# Ffrydiau_core.net
KiCad netlist of a schematic drawn in EAGLE
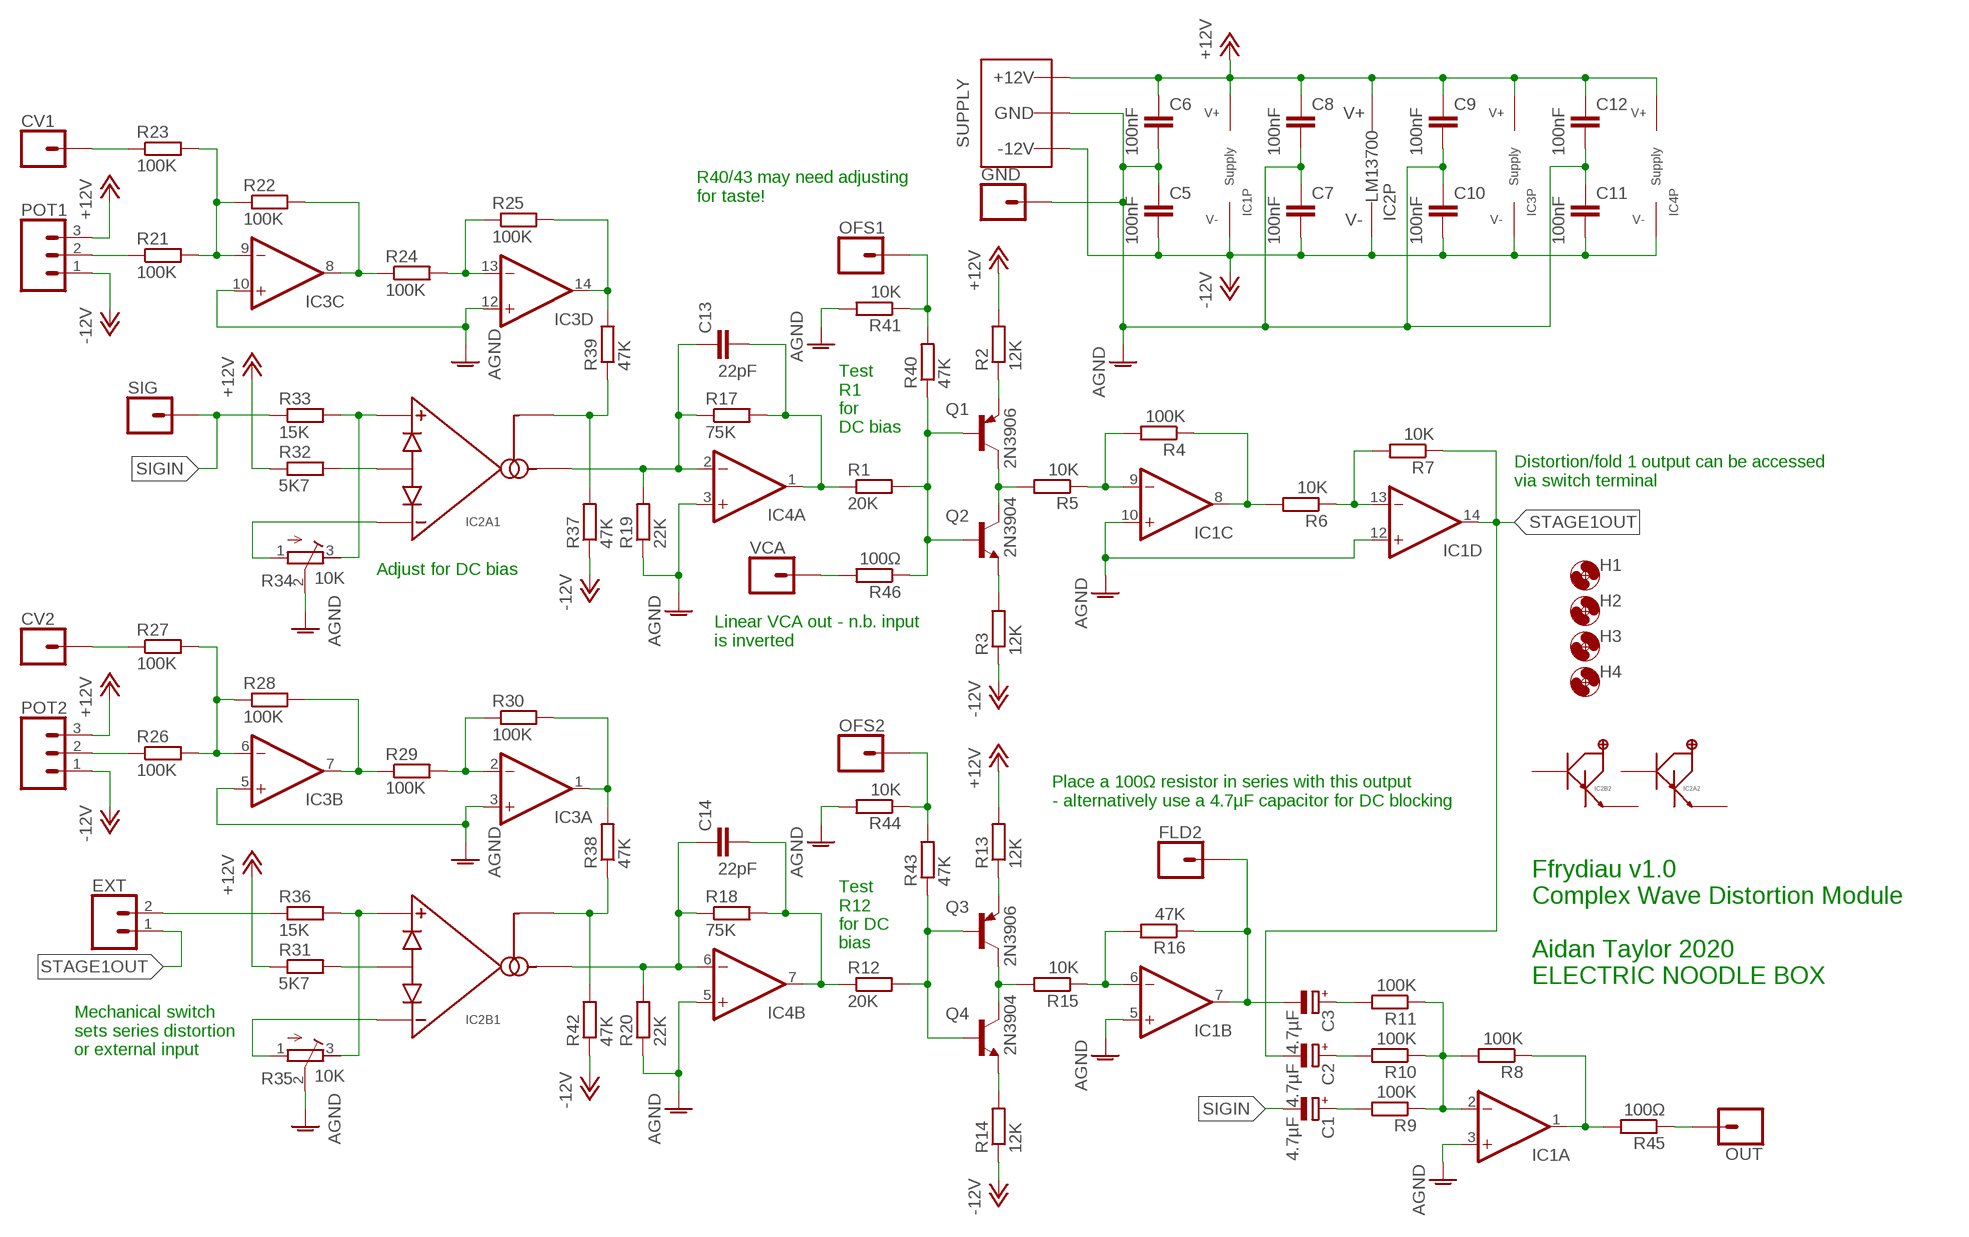
[diagram p0: schematic, sheet 1]

(export (version "E")
  (design (tool "Eeschema 10.0.6"))
  (components
    (comp (ref "C1")
      (value "4.7µF")
      (footprint "eagle-import:E2,5-6E")
      (libsource (lib "eagle-import") (part "CPOL-EUE2,5-6E"))
    )
    (comp (ref "C2")
      (value "4.7µF")
      (footprint "eagle-import:E2,5-6E")
      (libsource (lib "eagle-import") (part "CPOL-EUE2,5-6E"))
    )
    (comp (ref "C3")
      (value "4.7µF")
      (footprint "eagle-import:E2,5-6E")
      (libsource (lib "eagle-import") (part "CPOL-EUE2,5-6E"))
    )
    (comp (ref "C5")
      (value "100nF")
      (footprint "eagle-import:C050-025X075")
      (libsource (lib "eagle-import") (part "C-EU050-025X075"))
    )
    (comp (ref "C6")
      (value "100nF")
      (footprint "eagle-import:C050-025X075")
      (libsource (lib "eagle-import") (part "C-EU050-025X075"))
    )
    (comp (ref "C7")
      (value "100nF")
      (footprint "eagle-import:C050-025X075")
      (libsource (lib "eagle-import") (part "C-EU050-025X075"))
    )
    (comp (ref "C8")
      (value "100nF")
      (footprint "eagle-import:C050-025X075")
      (libsource (lib "eagle-import") (part "C-EU050-025X075"))
    )
    (comp (ref "C9")
      (value "100nF")
      (footprint "eagle-import:C050-025X075")
      (libsource (lib "eagle-import") (part "C-EU050-025X075"))
    )
    (comp (ref "C10")
      (value "100nF")
      (footprint "eagle-import:C050-025X075")
      (libsource (lib "eagle-import") (part "C-EU050-025X075"))
    )
    (comp (ref "C11")
      (value "100nF")
      (footprint "eagle-import:C050-025X075")
      (libsource (lib "eagle-import") (part "C-EU050-025X075"))
    )
    (comp (ref "C12")
      (value "100nF")
      (footprint "eagle-import:C050-025X075")
      (libsource (lib "eagle-import") (part "C-EU050-025X075"))
    )
    (comp (ref "C13")
      (value "22pF")
      (footprint "eagle-import:C050-025X075")
      (libsource (lib "eagle-import") (part "C-EU050-025X075"))
    )
    (comp (ref "C14")
      (value "22pF")
      (footprint "eagle-import:C050-025X075")
      (libsource (lib "eagle-import") (part "C-EU050-025X075"))
    )
    (comp (ref "CV1")
      (value "1XWIREPAD")
      (footprint "eagle-import:1X01")
      (libsource (lib "eagle-import") (part "1XWIREPAD"))
    )
    (comp (ref "CV2")
      (value "1XWIREPAD")
      (footprint "eagle-import:1X01")
      (libsource (lib "eagle-import") (part "1XWIREPAD"))
    )
    (comp (ref "EXT")
      (value "2XWIREPAD")
      (footprint "eagle-import:1X02")
      (libsource (lib "eagle-import") (part "2XWIREPAD"))
    )
    (comp (ref "FLD2")
      (value "1XWIREPAD")
      (footprint "eagle-import:1X01")
      (libsource (lib "eagle-import") (part "1XWIREPAD"))
    )
    (comp (ref "GND")
      (value "1XWIREPAD")
      (footprint "eagle-import:1X01")
      (libsource (lib "eagle-import") (part "1XWIREPAD"))
    )
    (comp (ref "H1")
      (value "MOUNT-HOLE3.2")
      (footprint "eagle-import:3,2")
      (libsource (lib "eagle-import") (part "MOUNT-HOLE3.2"))
    )
    (comp (ref "H2")
      (value "MOUNT-HOLE3.2")
      (footprint "eagle-import:3,2")
      (libsource (lib "eagle-import") (part "MOUNT-HOLE3.2"))
    )
    (comp (ref "H3")
      (value "MOUNT-HOLE3.2")
      (footprint "eagle-import:3,2")
      (libsource (lib "eagle-import") (part "MOUNT-HOLE3.2"))
    )
    (comp (ref "H4")
      (value "MOUNT-HOLE3.2")
      (footprint "eagle-import:3,2")
      (libsource (lib "eagle-import") (part "MOUNT-HOLE3.2"))
    )
    (comp (ref "IC1")
      (value "TL0X4DIL")
      (footprint "eagle-import:DIL14")
      (libsource (lib "eagle-import") (part "TL0X4DIL"))
    )
    (comp (ref "IC2")
      (value "LM13700DIL")
      (footprint "eagle-import:DIL16")
      (libsource (lib "eagle-import") (part "LM13700DIL"))
    )
    (comp (ref "IC3")
      (value "TL0X4DIL")
      (footprint "eagle-import:DIL14")
      (libsource (lib "eagle-import") (part "TL0X4DIL"))
    )
    (comp (ref "IC4")
      (value "TL0X2DIL")
      (footprint "eagle-import:DIL08")
      (libsource (lib "eagle-import") (part "TL0X2DIL"))
    )
    (comp (ref "OFS1")
      (value "1XWIREPAD")
      (footprint "eagle-import:1X01")
      (libsource (lib "eagle-import") (part "1XWIREPAD"))
    )
    (comp (ref "OFS2")
      (value "1XWIREPAD")
      (footprint "eagle-import:1X01")
      (libsource (lib "eagle-import") (part "1XWIREPAD"))
    )
    (comp (ref "OUT")
      (value "1XWIREPAD")
      (footprint "eagle-import:1X01")
      (libsource (lib "eagle-import") (part "1XWIREPAD"))
    )
    (comp (ref "POT1")
      (value "3XWIREPAD")
      (footprint "eagle-import:1X03")
      (libsource (lib "eagle-import") (part "3XWIREPAD"))
    )
    (comp (ref "POT2")
      (value "3XWIREPAD")
      (footprint "eagle-import:1X03")
      (libsource (lib "eagle-import") (part "3XWIREPAD"))
    )
    (comp (ref "Q1")
      (value "2N3906")
      (footprint "eagle-import:TO92")
      (libsource (lib "eagle-import") (part "2N3906"))
    )
    (comp (ref "Q2")
      (value "2N3904")
      (footprint "eagle-import:TO92")
      (libsource (lib "eagle-import") (part "2N3904"))
    )
    (comp (ref "Q3")
      (value "2N3906")
      (footprint "eagle-import:TO92")
      (libsource (lib "eagle-import") (part "2N3906"))
    )
    (comp (ref "Q4")
      (value "2N3904")
      (footprint "eagle-import:TO92")
      (libsource (lib "eagle-import") (part "2N3904"))
    )
    (comp (ref "R1")
      (value "20K")
      (footprint "eagle-import:0207_10")
      (libsource (lib "eagle-import") (part "R-EU_0207/10"))
    )
    (comp (ref "R2")
      (value "12K")
      (footprint "eagle-import:0207_10")
      (libsource (lib "eagle-import") (part "R-EU_0207/10"))
    )
    (comp (ref "R3")
      (value "12K")
      (footprint "eagle-import:0207_10")
      (libsource (lib "eagle-import") (part "R-EU_0207/10"))
    )
    (comp (ref "R4")
      (value "100K")
      (footprint "eagle-import:0207_10")
      (libsource (lib "eagle-import") (part "R-EU_0207/10"))
    )
    (comp (ref "R5")
      (value "10K")
      (footprint "eagle-import:0207_10")
      (libsource (lib "eagle-import") (part "R-EU_0207/10"))
    )
    (comp (ref "R6")
      (value "10K")
      (footprint "eagle-import:0207_10")
      (libsource (lib "eagle-import") (part "R-EU_0207/10"))
    )
    (comp (ref "R7")
      (value "10K")
      (footprint "eagle-import:0207_10")
      (libsource (lib "eagle-import") (part "R-EU_0207/10"))
    )
    (comp (ref "R8")
      (value "100K")
      (footprint "eagle-import:0207_10")
      (libsource (lib "eagle-import") (part "R-EU_0207/10"))
    )
    (comp (ref "R9")
      (value "100K")
      (footprint "eagle-import:0207_10")
      (libsource (lib "eagle-import") (part "R-EU_0207/10"))
    )
    (comp (ref "R10")
      (value "100K")
      (footprint "eagle-import:0207_10")
      (libsource (lib "eagle-import") (part "R-EU_0207/10"))
    )
    (comp (ref "R11")
      (value "100K")
      (footprint "eagle-import:0207_10")
      (libsource (lib "eagle-import") (part "R-EU_0207/10"))
    )
    (comp (ref "R12")
      (value "20K")
      (footprint "eagle-import:0207_10")
      (libsource (lib "eagle-import") (part "R-EU_0207/10"))
    )
    (comp (ref "R13")
      (value "12K")
      (footprint "eagle-import:0207_10")
      (libsource (lib "eagle-import") (part "R-EU_0207/10"))
    )
    (comp (ref "R14")
      (value "12K")
      (footprint "eagle-import:0207_10")
      (libsource (lib "eagle-import") (part "R-EU_0207/10"))
    )
    (comp (ref "R15")
      (value "10K")
      (footprint "eagle-import:0207_10")
      (libsource (lib "eagle-import") (part "R-EU_0207/10"))
    )
    (comp (ref "R16")
      (value "47K")
      (footprint "eagle-import:0207_10")
      (libsource (lib "eagle-import") (part "R-EU_0207/10"))
    )
    (comp (ref "R17")
      (value "75K")
      (footprint "eagle-import:0207_10")
      (libsource (lib "eagle-import") (part "R-EU_0207/10"))
    )
    (comp (ref "R18")
      (value "75K")
      (footprint "eagle-import:0207_10")
      (libsource (lib "eagle-import") (part "R-EU_0207/10"))
    )
    (comp (ref "R19")
      (value "22K")
      (footprint "eagle-import:0207_10")
      (libsource (lib "eagle-import") (part "R-EU_0207/10"))
    )
    (comp (ref "R20")
      (value "22K")
      (footprint "eagle-import:0207_10")
      (libsource (lib "eagle-import") (part "R-EU_0207/10"))
    )
    (comp (ref "R21")
      (value "100K")
      (footprint "eagle-import:0207_10")
      (libsource (lib "eagle-import") (part "R-EU_0207/10"))
    )
    (comp (ref "R22")
      (value "100K")
      (footprint "eagle-import:0207_10")
      (libsource (lib "eagle-import") (part "R-EU_0207/10"))
    )
    (comp (ref "R23")
      (value "100K")
      (footprint "eagle-import:0207_10")
      (libsource (lib "eagle-import") (part "R-EU_0207/10"))
    )
    (comp (ref "R24")
      (value "100K")
      (footprint "eagle-import:0207_10")
      (libsource (lib "eagle-import") (part "R-EU_0207/10"))
    )
    (comp (ref "R25")
      (value "100K")
      (footprint "eagle-import:0207_10")
      (libsource (lib "eagle-import") (part "R-EU_0207/10"))
    )
    (comp (ref "R26")
      (value "100K")
      (footprint "eagle-import:0207_10")
      (libsource (lib "eagle-import") (part "R-EU_0207/10"))
    )
    (comp (ref "R27")
      (value "100K")
      (footprint "eagle-import:0207_10")
      (libsource (lib "eagle-import") (part "R-EU_0207/10"))
    )
    (comp (ref "R28")
      (value "100K")
      (footprint "eagle-import:0207_10")
      (libsource (lib "eagle-import") (part "R-EU_0207/10"))
    )
    (comp (ref "R29")
      (value "100K")
      (footprint "eagle-import:0207_10")
      (libsource (lib "eagle-import") (part "R-EU_0207/10"))
    )
    (comp (ref "R30")
      (value "100K")
      (footprint "eagle-import:0207_10")
      (libsource (lib "eagle-import") (part "R-EU_0207/10"))
    )
    (comp (ref "R31")
      (value "5K7")
      (footprint "eagle-import:0207_10")
      (libsource (lib "eagle-import") (part "R-EU_0207/10"))
    )
    (comp (ref "R32")
      (value "5K7")
      (footprint "eagle-import:0207_10")
      (libsource (lib "eagle-import") (part "R-EU_0207/10"))
    )
    (comp (ref "R33")
      (value "15K")
      (footprint "eagle-import:0207_10")
      (libsource (lib "eagle-import") (part "R-EU_0207/10"))
    )
    (comp (ref "R34")
      (value "10K")
      (footprint "eagle-import:RTRIM3296W")
      (libsource (lib "eagle-import") (part "R-TRIMM3296W"))
    )
    (comp (ref "R35")
      (value "10K")
      (footprint "eagle-import:RTRIM3296W")
      (libsource (lib "eagle-import") (part "R-TRIMM3296W"))
    )
    (comp (ref "R36")
      (value "15K")
      (footprint "eagle-import:0207_10")
      (libsource (lib "eagle-import") (part "R-EU_0207/10"))
    )
    (comp (ref "R37")
      (value "47K")
      (footprint "eagle-import:0207_10")
      (libsource (lib "eagle-import") (part "R-EU_0207/10"))
    )
    (comp (ref "R38")
      (value "47K")
      (footprint "eagle-import:0207_10")
      (libsource (lib "eagle-import") (part "R-EU_0207/10"))
    )
    (comp (ref "R39")
      (value "47K")
      (footprint "eagle-import:0207_10")
      (libsource (lib "eagle-import") (part "R-EU_0207/10"))
    )
    (comp (ref "R40")
      (value "47K")
      (footprint "eagle-import:0207_10")
      (libsource (lib "eagle-import") (part "R-EU_0207/10"))
    )
    (comp (ref "R41")
      (value "10K")
      (footprint "eagle-import:0207_10")
      (libsource (lib "eagle-import") (part "R-EU_0207/10"))
    )
    (comp (ref "R42")
      (value "47K")
      (footprint "eagle-import:0207_10")
      (libsource (lib "eagle-import") (part "R-EU_0207/10"))
    )
    (comp (ref "R43")
      (value "47K")
      (footprint "eagle-import:0207_10")
      (libsource (lib "eagle-import") (part "R-EU_0207/10"))
    )
    (comp (ref "R44")
      (value "10K")
      (footprint "eagle-import:0207_10")
      (libsource (lib "eagle-import") (part "R-EU_0207/10"))
    )
    (comp (ref "R45")
      (value "100Ω")
      (footprint "eagle-import:0207_10")
      (libsource (lib "eagle-import") (part "R-EU_0207/10"))
    )
    (comp (ref "R46")
      (value "100Ω")
      (footprint "eagle-import:0207_10")
      (libsource (lib "eagle-import") (part "R-EU_0207/10"))
    )
    (comp (ref "SIG")
      (value "1XWIREPAD")
      (footprint "eagle-import:1X01")
      (libsource (lib "eagle-import") (part "1XWIREPAD"))
    )
    (comp (ref "VCA")
      (value "1XWIREPAD")
      (footprint "eagle-import:1X01")
      (libsource (lib "eagle-import") (part "1XWIREPAD"))
    )
    (comp (ref "WP1")
      (value "COMBO_SUPPLY_HEADER")
      (footprint "eagle-import:COMBINED_POWER")
      (libsource (lib "eagle-import") (part "COMBO_SUPPLY_HEADER"))
    )
  )
  (nets
    (net (code "1") (name "+12V") (class "Default")
      (node (ref "C12") (pin "1") (pinfunction "1_1") (pintype "passive"))
      (node (ref "C6") (pin "1") (pinfunction "1_1") (pintype "passive"))
      (node (ref "C8") (pin "1") (pinfunction "1_1") (pintype "passive"))
      (node (ref "C9") (pin "1") (pinfunction "1_1") (pintype "passive"))
      (node (ref "IC1") (pin "4") (pinfunction "V+_4") (pintype "bidirectional"))
      (node (ref "IC2") (pin "11") (pinfunction "V+_11") (pintype "power_in"))
      (node (ref "IC3") (pin "4") (pinfunction "V+_4") (pintype "bidirectional"))
      (node (ref "IC4") (pin "8") (pinfunction "V+_8") (pintype "bidirectional"))
      (node (ref "POT1") (pin "3") (pinfunction "3_3") (pintype "passive"))
      (node (ref "POT2") (pin "3") (pinfunction "3_3") (pintype "passive"))
      (node (ref "R13") (pin "2") (pinfunction "2_2") (pintype "passive"))
      (node (ref "R2") (pin "2") (pinfunction "2_2") (pintype "passive"))
      (node (ref "R31") (pin "1") (pinfunction "1_1") (pintype "passive"))
      (node (ref "R32") (pin "1") (pinfunction "1_1") (pintype "passive"))
      (node (ref "WP1") (pin "V+1") (pinfunction "V++_V+1") (pintype "power_in"))
      (node (ref "WP1") (pin "V+2") (pinfunction "V++_V+2") (pintype "power_in"))
      (node (ref "WP1") (pin "V+3") (pinfunction "V++_V+3") (pintype "power_in"))
    )
    (net (code "2") (name "-12V") (class "Default")
      (node (ref "C10") (pin "2") (pinfunction "2_2") (pintype "passive"))
      (node (ref "C11") (pin "2") (pinfunction "2_2") (pintype "passive"))
      (node (ref "C5") (pin "2") (pinfunction "2_2") (pintype "passive"))
      (node (ref "C7") (pin "2") (pinfunction "2_2") (pintype "passive"))
      (node (ref "IC1") (pin "11") (pinfunction "V-_11") (pintype "bidirectional"))
      (node (ref "IC2") (pin "6") (pinfunction "V-_6") (pintype "power_in"))
      (node (ref "IC3") (pin "11") (pinfunction "V-_11") (pintype "bidirectional"))
      (node (ref "IC4") (pin "4") (pinfunction "V-_4") (pintype "bidirectional"))
      (node (ref "POT1") (pin "1") (pinfunction "1_1") (pintype "passive"))
      (node (ref "POT2") (pin "1") (pinfunction "1_1") (pintype "passive"))
      (node (ref "R14") (pin "1") (pinfunction "1_1") (pintype "passive"))
      (node (ref "R3") (pin "1") (pinfunction "1_1") (pintype "passive"))
      (node (ref "R37") (pin "1") (pinfunction "1_1") (pintype "passive"))
      (node (ref "R42") (pin "1") (pinfunction "1_1") (pintype "passive"))
      (node (ref "WP1") (pin "V-1") (pinfunction "V--_V-1") (pintype "power_in"))
      (node (ref "WP1") (pin "V-2") (pinfunction "V--_V-2") (pintype "power_in"))
      (node (ref "WP1") (pin "V-3") (pinfunction "V--_V-3") (pintype "power_in"))
    )
    (net (code "3") (name "AGND") (class "Default")
      (node (ref "C10") (pin "1") (pinfunction "1_1") (pintype "passive"))
      (node (ref "C11") (pin "1") (pinfunction "1_1") (pintype "passive"))
      (node (ref "C12") (pin "2") (pinfunction "2_2") (pintype "passive"))
      (node (ref "C5") (pin "1") (pinfunction "1_1") (pintype "passive"))
      (node (ref "C6") (pin "2") (pinfunction "2_2") (pintype "passive"))
      (node (ref "C7") (pin "1") (pinfunction "1_1") (pintype "passive"))
      (node (ref "C8") (pin "2") (pinfunction "2_2") (pintype "passive"))
      (node (ref "C9") (pin "2") (pinfunction "2_2") (pintype "passive"))
      (node (ref "GND") (pin "1") (pinfunction "1_1") (pintype "passive"))
      (node (ref "IC1") (pin "10") (pinfunction "+IN_10") (pintype "input"))
      (node (ref "IC1") (pin "12") (pinfunction "+IN_12") (pintype "input"))
      (node (ref "IC1") (pin "3") (pinfunction "+IN_3") (pintype "input"))
      (node (ref "IC1") (pin "5") (pinfunction "+IN_5") (pintype "input"))
      (node (ref "IC3") (pin "10") (pinfunction "+IN_10") (pintype "input"))
      (node (ref "IC3") (pin "12") (pinfunction "+IN_12") (pintype "input"))
      (node (ref "IC3") (pin "3") (pinfunction "+IN_3") (pintype "input"))
      (node (ref "IC3") (pin "5") (pinfunction "+IN_5") (pintype "input"))
      (node (ref "IC4") (pin "3") (pinfunction "+IN_3") (pintype "input"))
      (node (ref "IC4") (pin "5") (pinfunction "+IN_5") (pintype "input"))
      (node (ref "R19") (pin "1") (pinfunction "1_1") (pintype "passive"))
      (node (ref "R20") (pin "1") (pinfunction "1_1") (pintype "passive"))
      (node (ref "R34") (pin "2") (pinfunction "S_2") (pintype "passive"))
      (node (ref "R35") (pin "2") (pinfunction "S_2") (pintype "passive"))
      (node (ref "R41") (pin "2") (pinfunction "2_2") (pintype "passive"))
      (node (ref "R44") (pin "2") (pinfunction "2_2") (pintype "passive"))
      (node (ref "WP1") (pin "GND1") (pinfunction "AGND_GND1") (pintype "power_in"))
      (node (ref "WP1") (pin "GND2") (pinfunction "AGND_GND2") (pintype "power_in"))
      (node (ref "WP1") (pin "GND3") (pinfunction "AGND_GND3") (pintype "power_in"))
      (node (ref "WP1") (pin "GND4") (pinfunction "AGND_GND4") (pintype "power_in"))
      (node (ref "WP1") (pin "GND5") (pinfunction "AGND_GND5") (pintype "power_in"))
      (node (ref "WP1") (pin "GND6") (pinfunction "AGND_GND6") (pintype "power_in"))
      (node (ref "WP1") (pin "GND7") (pinfunction "AGND_GND7") (pintype "power_in"))
      (node (ref "WP1") (pin "GND8") (pinfunction "AGND_GND8") (pintype "power_in"))
    )
    (net (code "4") (name "Net-(C1-Pad+)") (class "Default")
      (node (ref "C1") (pin "+") (pinfunction "+_+") (pintype "passive"))
      (node (ref "R9") (pin "2") (pinfunction "2_2") (pintype "passive"))
    )
    (net (code "5") (name "Net-(C2-Pad+)") (class "Default")
      (node (ref "C2") (pin "+") (pinfunction "+_+") (pintype "passive"))
      (node (ref "R10") (pin "2") (pinfunction "2_2") (pintype "passive"))
    )
    (net (code "6") (name "Net-(C3-Pad+)") (class "Default")
      (node (ref "C3") (pin "+") (pinfunction "+_+") (pintype "passive"))
      (node (ref "R11") (pin "2") (pinfunction "2_2") (pintype "passive"))
    )
    (net (code "7") (name "Net-(CV1-Pad1)") (class "Default")
      (node (ref "CV1") (pin "1") (pinfunction "1_1") (pintype "passive"))
      (node (ref "R23") (pin "1") (pinfunction "1_1") (pintype "passive"))
    )
    (net (code "8") (name "Net-(CV2-Pad1)") (class "Default")
      (node (ref "CV2") (pin "1") (pinfunction "1_1") (pintype "passive"))
      (node (ref "R27") (pin "1") (pinfunction "1_1") (pintype "passive"))
    )
    (net (code "9") (name "Net-(EXT-Pad2)") (class "Default")
      (node (ref "EXT") (pin "2") (pinfunction "2_2") (pintype "passive"))
      (node (ref "R36") (pin "1") (pinfunction "1_1") (pintype "passive"))
    )
    (net (code "10") (name "Net-(IC1A--IN)") (class "Default")
      (node (ref "IC1") (pin "2") (pinfunction "-IN_2") (pintype "input"))
      (node (ref "R10") (pin "1") (pinfunction "1_1") (pintype "passive"))
      (node (ref "R11") (pin "1") (pinfunction "1_1") (pintype "passive"))
      (node (ref "R8") (pin "2") (pinfunction "2_2") (pintype "passive"))
      (node (ref "R9") (pin "1") (pinfunction "1_1") (pintype "passive"))
    )
    (net (code "11") (name "Net-(IC1A-OUT)") (class "Default")
      (node (ref "IC1") (pin "1") (pinfunction "OUT_1") (pintype "output"))
      (node (ref "R45") (pin "2") (pinfunction "2_2") (pintype "passive"))
      (node (ref "R8") (pin "1") (pinfunction "1_1") (pintype "passive"))
    )
    (net (code "12") (name "Net-(IC1B--IN)") (class "Default")
      (node (ref "IC1") (pin "6") (pinfunction "-IN_6") (pintype "input"))
      (node (ref "R15") (pin "1") (pinfunction "1_1") (pintype "passive"))
      (node (ref "R16") (pin "2") (pinfunction "2_2") (pintype "passive"))
    )
    (net (code "13") (name "Net-(IC1B-OUT)") (class "Default")
      (node (ref "C3") (pin "-") (pinfunction "-_-") (pintype "passive"))
      (node (ref "FLD2") (pin "1") (pinfunction "1_1") (pintype "passive"))
      (node (ref "IC1") (pin "7") (pinfunction "OUT_7") (pintype "output"))
      (node (ref "R16") (pin "1") (pinfunction "1_1") (pintype "passive"))
    )
    (net (code "14") (name "Net-(IC1C--IN)") (class "Default")
      (node (ref "IC1") (pin "9") (pinfunction "-IN_9") (pintype "input"))
      (node (ref "R4") (pin "2") (pinfunction "2_2") (pintype "passive"))
      (node (ref "R5") (pin "1") (pinfunction "1_1") (pintype "passive"))
    )
    (net (code "15") (name "Net-(IC1C-OUT)") (class "Default")
      (node (ref "IC1") (pin "8") (pinfunction "OUT_8") (pintype "output"))
      (node (ref "R4") (pin "1") (pinfunction "1_1") (pintype "passive"))
      (node (ref "R6") (pin "2") (pinfunction "2_2") (pintype "passive"))
    )
    (net (code "16") (name "Net-(IC1D--IN)") (class "Default")
      (node (ref "IC1") (pin "13") (pinfunction "-IN_13") (pintype "input"))
      (node (ref "R6") (pin "1") (pinfunction "1_1") (pintype "passive"))
      (node (ref "R7") (pin "2") (pinfunction "2_2") (pintype "passive"))
    )
    (net (code "17") (name "Net-(IC2A-AMP+)") (class "Default")
      (node (ref "IC2") (pin "3") (pinfunction "AMP+_3") (pintype "input"))
      (node (ref "R33") (pin "2") (pinfunction "2_2") (pintype "passive"))
      (node (ref "R34") (pin "3") (pinfunction "E_3") (pintype "passive"))
    )
    (net (code "18") (name "Net-(IC2A-AMP-)") (class "Default")
      (node (ref "IC2") (pin "4") (pinfunction "AMP-_4") (pintype "input"))
      (node (ref "R34") (pin "1") (pinfunction "A_1") (pintype "passive"))
    )
    (net (code "19") (name "Net-(IC2A-AMPBIAS)") (class "Default")
      (node (ref "IC2") (pin "1") (pinfunction "AMPBIAS_1") (pintype "input"))
      (node (ref "R37") (pin "2") (pinfunction "2_2") (pintype "passive"))
      (node (ref "R39") (pin "1") (pinfunction "1_1") (pintype "passive"))
    )
    (net (code "20") (name "Net-(IC2A-AMPOUT)") (class "Default")
      (node (ref "C13") (pin "1") (pinfunction "1_1") (pintype "passive"))
      (node (ref "IC2") (pin "5") (pinfunction "AMPOUT_5") (pintype "output"))
      (node (ref "IC4") (pin "2") (pinfunction "-IN_2") (pintype "input"))
      (node (ref "R17") (pin "1") (pinfunction "1_1") (pintype "passive"))
      (node (ref "R19") (pin "2") (pinfunction "2_2") (pintype "passive"))
    )
    (net (code "21") (name "Net-(IC2A-DIODES)") (class "Default")
      (node (ref "IC2") (pin "2") (pinfunction "DIODES_2") (pintype "input"))
      (node (ref "R32") (pin "2") (pinfunction "2_2") (pintype "passive"))
    )
    (net (code "22") (name "Net-(IC2C-AMP+)") (class "Default")
      (node (ref "IC2") (pin "14") (pinfunction "AMP+_14") (pintype "input"))
      (node (ref "R35") (pin "3") (pinfunction "E_3") (pintype "passive"))
      (node (ref "R36") (pin "2") (pinfunction "2_2") (pintype "passive"))
    )
    (net (code "23") (name "Net-(IC2C-AMP-)") (class "Default")
      (node (ref "IC2") (pin "13") (pinfunction "AMP-_13") (pintype "input"))
      (node (ref "R35") (pin "1") (pinfunction "A_1") (pintype "passive"))
    )
    (net (code "24") (name "Net-(IC2C-AMPBIAS)") (class "Default")
      (node (ref "IC2") (pin "16") (pinfunction "AMPBIAS_16") (pintype "input"))
      (node (ref "R38") (pin "1") (pinfunction "1_1") (pintype "passive"))
      (node (ref "R42") (pin "2") (pinfunction "2_2") (pintype "passive"))
    )
    (net (code "25") (name "Net-(IC2C-AMPOUT)") (class "Default")
      (node (ref "C14") (pin "1") (pinfunction "1_1") (pintype "passive"))
      (node (ref "IC2") (pin "12") (pinfunction "AMPOUT_12") (pintype "output"))
      (node (ref "IC4") (pin "6") (pinfunction "-IN_6") (pintype "input"))
      (node (ref "R18") (pin "1") (pinfunction "1_1") (pintype "passive"))
      (node (ref "R20") (pin "2") (pinfunction "2_2") (pintype "passive"))
    )
    (net (code "26") (name "Net-(IC2C-DIODES)") (class "Default")
      (node (ref "IC2") (pin "15") (pinfunction "DIODES_15") (pintype "input"))
      (node (ref "R31") (pin "2") (pinfunction "2_2") (pintype "passive"))
    )
    (net (code "27") (name "Net-(IC3A--IN)") (class "Default")
      (node (ref "IC3") (pin "2") (pinfunction "-IN_2") (pintype "input"))
      (node (ref "R29") (pin "2") (pinfunction "2_2") (pintype "passive"))
      (node (ref "R30") (pin "1") (pinfunction "1_1") (pintype "passive"))
    )
    (net (code "28") (name "Net-(IC3A-OUT)") (class "Default")
      (node (ref "IC3") (pin "1") (pinfunction "OUT_1") (pintype "output"))
      (node (ref "R30") (pin "2") (pinfunction "2_2") (pintype "passive"))
      (node (ref "R38") (pin "2") (pinfunction "2_2") (pintype "passive"))
    )
    (net (code "29") (name "Net-(IC3B--IN)") (class "Default")
      (node (ref "IC3") (pin "6") (pinfunction "-IN_6") (pintype "input"))
      (node (ref "R26") (pin "2") (pinfunction "2_2") (pintype "passive"))
      (node (ref "R27") (pin "2") (pinfunction "2_2") (pintype "passive"))
      (node (ref "R28") (pin "1") (pinfunction "1_1") (pintype "passive"))
    )
    (net (code "30") (name "Net-(IC3B-OUT)") (class "Default")
      (node (ref "IC3") (pin "7") (pinfunction "OUT_7") (pintype "output"))
      (node (ref "R28") (pin "2") (pinfunction "2_2") (pintype "passive"))
      (node (ref "R29") (pin "1") (pinfunction "1_1") (pintype "passive"))
    )
    (net (code "31") (name "Net-(IC3C--IN)") (class "Default")
      (node (ref "IC3") (pin "9") (pinfunction "-IN_9") (pintype "input"))
      (node (ref "R21") (pin "2") (pinfunction "2_2") (pintype "passive"))
      (node (ref "R22") (pin "1") (pinfunction "1_1") (pintype "passive"))
      (node (ref "R23") (pin "2") (pinfunction "2_2") (pintype "passive"))
    )
    (net (code "32") (name "Net-(IC3C-OUT)") (class "Default")
      (node (ref "IC3") (pin "8") (pinfunction "OUT_8") (pintype "output"))
      (node (ref "R22") (pin "2") (pinfunction "2_2") (pintype "passive"))
      (node (ref "R24") (pin "1") (pinfunction "1_1") (pintype "passive"))
    )
    (net (code "33") (name "Net-(IC3D--IN)") (class "Default")
      (node (ref "IC3") (pin "13") (pinfunction "-IN_13") (pintype "input"))
      (node (ref "R24") (pin "2") (pinfunction "2_2") (pintype "passive"))
      (node (ref "R25") (pin "1") (pinfunction "1_1") (pintype "passive"))
    )
    (net (code "34") (name "Net-(IC3D-OUT)") (class "Default")
      (node (ref "IC3") (pin "14") (pinfunction "OUT_14") (pintype "output"))
      (node (ref "R25") (pin "2") (pinfunction "2_2") (pintype "passive"))
      (node (ref "R39") (pin "2") (pinfunction "2_2") (pintype "passive"))
    )
    (net (code "35") (name "Net-(IC4A-OUT)") (class "Default")
      (node (ref "C13") (pin "2") (pinfunction "2_2") (pintype "passive"))
      (node (ref "IC4") (pin "1") (pinfunction "OUT_1") (pintype "output"))
      (node (ref "R1") (pin "1") (pinfunction "1_1") (pintype "passive"))
      (node (ref "R17") (pin "2") (pinfunction "2_2") (pintype "passive"))
    )
    (net (code "36") (name "Net-(IC4B-OUT)") (class "Default")
      (node (ref "C14") (pin "2") (pinfunction "2_2") (pintype "passive"))
      (node (ref "IC4") (pin "7") (pinfunction "OUT_7") (pintype "output"))
      (node (ref "R12") (pin "1") (pinfunction "1_1") (pintype "passive"))
      (node (ref "R18") (pin "2") (pinfunction "2_2") (pintype "passive"))
    )
    (net (code "37") (name "Net-(OFS1-Pad1)") (class "Default")
      (node (ref "OFS1") (pin "1") (pinfunction "1_1") (pintype "passive"))
      (node (ref "R40") (pin "2") (pinfunction "2_2") (pintype "passive"))
      (node (ref "R41") (pin "1") (pinfunction "1_1") (pintype "passive"))
    )
    (net (code "38") (name "Net-(OFS2-Pad1)") (class "Default")
      (node (ref "OFS2") (pin "1") (pinfunction "1_1") (pintype "passive"))
      (node (ref "R43") (pin "2") (pinfunction "2_2") (pintype "passive"))
      (node (ref "R44") (pin "1") (pinfunction "1_1") (pintype "passive"))
    )
    (net (code "39") (name "Net-(OUT-Pad1)") (class "Default")
      (node (ref "OUT") (pin "1") (pinfunction "1_1") (pintype "passive"))
      (node (ref "R45") (pin "1") (pinfunction "1_1") (pintype "passive"))
    )
    (net (code "40") (name "Net-(POT1-Pad2)") (class "Default")
      (node (ref "POT1") (pin "2") (pinfunction "2_2") (pintype "passive"))
      (node (ref "R21") (pin "1") (pinfunction "1_1") (pintype "passive"))
    )
    (net (code "41") (name "Net-(POT2-Pad2)") (class "Default")
      (node (ref "POT2") (pin "2") (pinfunction "2_2") (pintype "passive"))
      (node (ref "R26") (pin "1") (pinfunction "1_1") (pintype "passive"))
    )
    (net (code "42") (name "Net-(Q1-B)") (class "Default")
      (node (ref "Q1") (pin "2") (pinfunction "B_2") (pintype "passive"))
      (node (ref "Q2") (pin "2") (pinfunction "B_2") (pintype "passive"))
      (node (ref "R1") (pin "2") (pinfunction "2_2") (pintype "passive"))
      (node (ref "R40") (pin "1") (pinfunction "1_1") (pintype "passive"))
      (node (ref "R46") (pin "1") (pinfunction "1_1") (pintype "passive"))
    )
    (net (code "43") (name "Net-(Q1-C)") (class "Default")
      (node (ref "Q1") (pin "1") (pinfunction "C_1") (pintype "passive"))
      (node (ref "Q2") (pin "1") (pinfunction "C_1") (pintype "passive"))
      (node (ref "R5") (pin "2") (pinfunction "2_2") (pintype "passive"))
    )
    (net (code "44") (name "Net-(Q1-E)") (class "Default")
      (node (ref "Q1") (pin "3") (pinfunction "E_3") (pintype "passive"))
      (node (ref "R2") (pin "1") (pinfunction "1_1") (pintype "passive"))
    )
    (net (code "45") (name "Net-(Q2-E)") (class "Default")
      (node (ref "Q2") (pin "3") (pinfunction "E_3") (pintype "passive"))
      (node (ref "R3") (pin "2") (pinfunction "2_2") (pintype "passive"))
    )
    (net (code "46") (name "Net-(Q3-B)") (class "Default")
      (node (ref "Q3") (pin "2") (pinfunction "B_2") (pintype "passive"))
      (node (ref "Q4") (pin "2") (pinfunction "B_2") (pintype "passive"))
      (node (ref "R12") (pin "2") (pinfunction "2_2") (pintype "passive"))
      (node (ref "R43") (pin "1") (pinfunction "1_1") (pintype "passive"))
    )
    (net (code "47") (name "Net-(Q3-C)") (class "Default")
      (node (ref "Q3") (pin "1") (pinfunction "C_1") (pintype "passive"))
      (node (ref "Q4") (pin "1") (pinfunction "C_1") (pintype "passive"))
      (node (ref "R15") (pin "2") (pinfunction "2_2") (pintype "passive"))
    )
    (net (code "48") (name "Net-(Q3-E)") (class "Default")
      (node (ref "Q3") (pin "3") (pinfunction "E_3") (pintype "passive"))
      (node (ref "R13") (pin "1") (pinfunction "1_1") (pintype "passive"))
    )
    (net (code "49") (name "Net-(Q4-E)") (class "Default")
      (node (ref "Q4") (pin "3") (pinfunction "E_3") (pintype "passive"))
      (node (ref "R14") (pin "2") (pinfunction "2_2") (pintype "passive"))
    )
    (net (code "50") (name "Net-(R46-Pad2)") (class "Default")
      (node (ref "R46") (pin "2") (pinfunction "2_2") (pintype "passive"))
      (node (ref "VCA") (pin "1") (pinfunction "1_1") (pintype "passive"))
    )
    (net (code "51") (name "SIGIN") (class "Default")
      (node (ref "C1") (pin "-") (pinfunction "-_-") (pintype "passive"))
      (node (ref "R33") (pin "1") (pinfunction "1_1") (pintype "passive"))
      (node (ref "SIG") (pin "1") (pinfunction "1_1") (pintype "passive"))
    )
    (net (code "52") (name "STAGE1OUT") (class "Default")
      (node (ref "C2") (pin "-") (pinfunction "-_-") (pintype "passive"))
      (node (ref "EXT") (pin "1") (pinfunction "1_1") (pintype "passive"))
      (node (ref "IC1") (pin "14") (pinfunction "OUT_14") (pintype "output"))
      (node (ref "R7") (pin "1") (pinfunction "1_1") (pintype "passive"))
    )
    (net (code "53") (name "unconnected-(IC2B-BUFF_IN-Pad7)") (class "Default")
      (node (ref "IC2") (pin "7") (pinfunction "BUFF_IN_7") (pintype "input"))
    )
    (net (code "54") (name "unconnected-(IC2B-BUFF_OUT-Pad8)") (class "Default")
      (node (ref "IC2") (pin "8") (pinfunction "BUFF_OUT_8") (pintype "bidirectional"))
    )
    (net (code "55") (name "unconnected-(IC2D-BUFF_IN-Pad10)") (class "Default")
      (node (ref "IC2") (pin "10") (pinfunction "BUFF_IN_10") (pintype "input"))
    )
    (net (code "56") (name "unconnected-(IC2D-BUFF_OUT-Pad9)") (class "Default")
      (node (ref "IC2") (pin "9") (pinfunction "BUFF_OUT_9") (pintype "bidirectional"))
    )
  )
)
